# ServoPower.net
KiCad netlist of a schematic drawn in Altium Designer
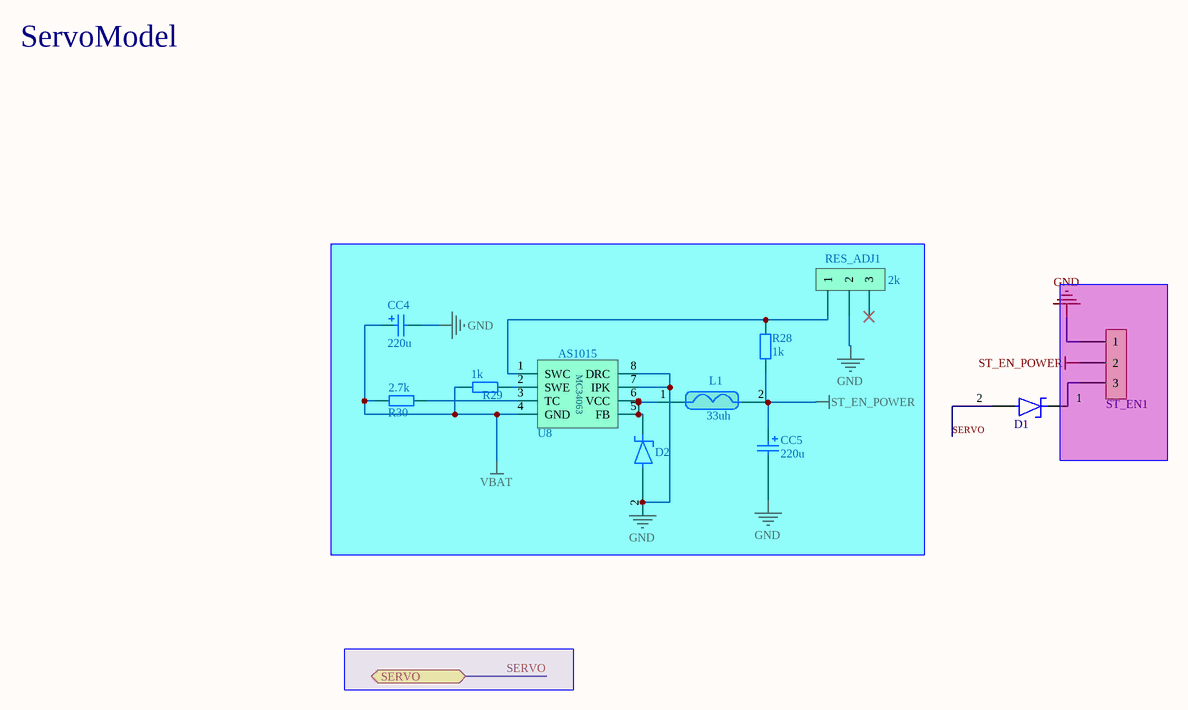
[diagram p0: ServoPower.SchDoc]

(export (version "E")
  (design (tool "Eeschema 10.0.6"))
  (components
    (comp (ref "CC4")
      (value "Cap Tan C")
      (footprint "CAPMP6032X26N")
      (description "Polarized Capacitor (Radial)")
      (fields
        (field (name "CAPACITANCE") "220u")
        (field (name "VOLTAGE") "16V")
        (field (name "PUBLISHER") "Altium Limited")
      )
      (libsource (lib "ZZCDevice") (part "Cap Tan C"))
    )
    (comp (ref "CC5")
      (value "Cap Tan C")
      (footprint "CAPMP6032X26N")
      (description "Polarized Capacitor (Radial)")
      (fields
        (field (name "CAPACITANCE") "220u")
        (field (name "VOLTAGE") "16V")
        (field (name "PUBLISHER") "Altium Limited")
      )
      (libsource (lib "ZZCDevice") (part "Cap Tan C"))
    )
    (comp (ref "D1") (value "贴片二极管") (footprint "二极管SMA") (libsource (lib "常用原件库") (part "贴片二极管")))
    (comp (ref "D2") (value "贴片二极管") (footprint "二极管SMA") (libsource (lib "常用原件库") (part "贴片二极管")))
    (comp (ref "L1") (value "33uh") (footprint "电感7.3X7.3") (libsource (lib "常用原件库") (part "电感")))
    (comp (ref "R28") (value "1k") (footprint "0805电阻") (libsource (lib "常用原件库") (part "0805电阻")))
    (comp (ref "R29") (value "1k") (footprint "0805电阻") (libsource (lib "常用原件库") (part "0805电阻")))
    (comp (ref "R30") (value "2.7k") (footprint "0805电阻") (libsource (lib "常用原件库") (part "0805电阻")))
    (comp (ref "RES_ADJ1") (value "2k") (footprint "Header3") (libsource (lib "") (part "Header3_1")))
    (comp (ref "ST_EN1") (value "Header3") (footprint "Header3") (libsource (lib "常用原件库") (part "Header3")))
    (comp (ref "U8") (value "AS1015") (footprint "MC34063") (libsource (lib "常用原件库") (part "MC34063")))
  )
  (nets
    (net (code "1") (name "/SERVO") (class "Default")
      (node (ref "D1") (pin "2") (pinfunction "2_2") (pintype "passive"))
    )
    (net (code "2") (name "GND") (class "Default")
      (node (ref "CC4") (pin "1") (pinfunction "2_1") (pintype "passive"))
      (node (ref "CC5") (pin "1") (pinfunction "2_1") (pintype "passive"))
      (node (ref "D2") (pin "2") (pinfunction "2_2") (pintype "passive"))
      (node (ref "RES_ADJ1") (pin "2") (pinfunction "2_2") (pintype "passive"))
      (node (ref "ST_EN1") (pin "1") (pinfunction "1_1") (pintype "passive"))
      (node (ref "U8") (pin "7") (pinfunction "IPK_7") (pintype "passive"))
      (node (ref "U8") (pin "8") (pinfunction "DRC_8") (pintype "passive"))
    )
    (net (code "3") (name "Net-(D1-Pad1)") (class "Default")
      (node (ref "D1") (pin "1") (pinfunction "1_1") (pintype "passive"))
      (node (ref "ST_EN1") (pin "3") (pinfunction "3_3") (pintype "passive"))
    )
    (net (code "4") (name "Net-(U8-FB)") (class "Default")
      (node (ref "D2") (pin "1") (pinfunction "1_1") (pintype "passive"))
      (node (ref "L1") (pin "1") (pinfunction "1_1") (pintype "passive"))
      (node (ref "U8") (pin "5") (pinfunction "FB_5") (pintype "passive"))
      (node (ref "U8") (pin "6") (pinfunction "VCC_6") (pintype "passive"))
    )
    (net (code "5") (name "Net-(U8-SWC)") (class "Default")
      (node (ref "R28") (pin "2") (pinfunction "2_2") (pintype "passive"))
      (node (ref "RES_ADJ1") (pin "1") (pinfunction "1_1") (pintype "passive"))
      (node (ref "U8") (pin "1") (pinfunction "SWC_1") (pintype "passive"))
    )
    (net (code "6") (name "Net-(U8-SWE)") (class "Default")
      (node (ref "R29") (pin "2") (pinfunction "2_2") (pintype "passive"))
      (node (ref "U8") (pin "2") (pinfunction "SWE_2") (pintype "passive"))
    )
    (net (code "7") (name "Net-(U8-TC)") (class "Default")
      (node (ref "R30") (pin "2") (pinfunction "2_2") (pintype "passive"))
      (node (ref "U8") (pin "3") (pinfunction "TC_3") (pintype "passive"))
    )
    (net (code "8") (name "ST_EN_POWER") (class "Default")
      (node (ref "CC5") (pin "2") (pinfunction "1_2") (pintype "passive"))
      (node (ref "L1") (pin "2") (pinfunction "2_2") (pintype "passive"))
      (node (ref "R28") (pin "1") (pinfunction "1_1") (pintype "passive"))
      (node (ref "ST_EN1") (pin "2") (pinfunction "2_2") (pintype "passive"))
    )
    (net (code "9") (name "VBAT") (class "Default")
      (node (ref "CC4") (pin "2") (pinfunction "1_2") (pintype "passive"))
      (node (ref "R29") (pin "1") (pinfunction "1_1") (pintype "passive"))
      (node (ref "R30") (pin "1") (pinfunction "1_1") (pintype "passive"))
      (node (ref "U8") (pin "4") (pinfunction "GND_4") (pintype "passive"))
    )
    (net (code "10") (name "unconnected-(RES_ADJ1-Pad3)") (class "Default")
      (node (ref "RES_ADJ1") (pin "3") (pinfunction "3_3") (pintype "passive+no_connect"))
    )
  )
)
